# board.net
KiCad netlist of a schematic drawn in EAGLE
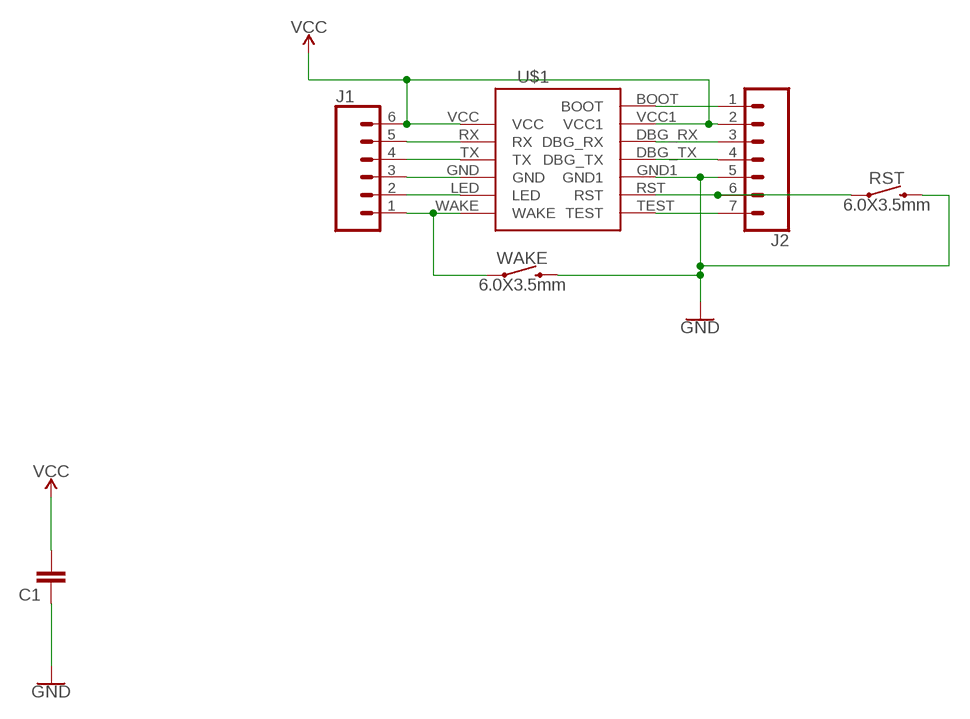
[diagram p0: schematic, sheet 1]

(export (version "E")
  (design (tool "Eeschema 10.0.6"))
  (components
    (comp (ref "C1")
      (value "C-EUC0805")
      (footprint "eagle-import:C0805")
      (libsource (lib "eagle-import") (part "C-EUC0805"))
    )
    (comp (ref "J1")
      (value "CONN_06LOCK")
      (footprint "eagle-import:1X06_LOCK")
      (libsource (lib "eagle-import") (part "CONN_06LOCK"))
    )
    (comp (ref "J2")
      (value "CONN_07LOCK")
      (footprint "eagle-import:1X07_LOCK")
      (libsource (lib "eagle-import") (part "CONN_07LOCK"))
    )
    (comp (ref "RST")
      (value "6.0X3.5mm")
      (footprint "eagle-import:TACTILE_SWITCH_SMD_6.0X3.5MM")
      (libsource (lib "eagle-import") (part "MOMENTARY-SWITCH-SPST-SMD-6.0X3.5MM"))
    )
    (comp (ref "U$1")
      (value "IM-L400")
      (footprint "eagle-import:IM-L400")
      (libsource (lib "eagle-import") (part "IM-L400"))
    )
    (comp (ref "WAKE")
      (value "6.0X3.5mm")
      (footprint "eagle-import:TACTILE_SWITCH_SMD_6.0X3.5MM")
      (libsource (lib "eagle-import") (part "MOMENTARY-SWITCH-SPST-SMD-6.0X3.5MM"))
    )
  )
  (nets
    (net (code "1") (name "GND") (class "Default")
      (node (ref "C1") (pin "1") (pinfunction "1_1") (pintype "passive"))
      (node (ref "J1") (pin "3") (pinfunction "3_3") (pintype "passive"))
      (node (ref "J2") (pin "5") (pinfunction "5_5") (pintype "passive"))
      (node (ref "RST") (pin "2") (pinfunction "2_2") (pintype "passive"))
      (node (ref "U$1") (pin "GND") (pinfunction "GND_GND") (pintype "bidirectional"))
      (node (ref "U$1") (pin "GND1") (pinfunction "GND1_GND1") (pintype "bidirectional"))
      (node (ref "WAKE") (pin "2") (pinfunction "2_2") (pintype "passive"))
    )
    (net (code "2") (name "Net-(J1-Pad1)") (class "Default")
      (node (ref "J1") (pin "1") (pinfunction "1_1") (pintype "passive"))
      (node (ref "U$1") (pin "WAKE") (pinfunction "WAKE_WAKE") (pintype "bidirectional"))
      (node (ref "WAKE") (pin "1") (pinfunction "1_1") (pintype "passive"))
    )
    (net (code "3") (name "Net-(J1-Pad2)") (class "Default")
      (node (ref "J1") (pin "2") (pinfunction "2_2") (pintype "passive"))
      (node (ref "U$1") (pin "LED") (pinfunction "LED_LED") (pintype "bidirectional"))
    )
    (net (code "4") (name "Net-(J1-Pad4)") (class "Default")
      (node (ref "J1") (pin "4") (pinfunction "4_4") (pintype "passive"))
      (node (ref "U$1") (pin "TX") (pinfunction "TX_TX") (pintype "bidirectional"))
    )
    (net (code "5") (name "Net-(J1-Pad5)") (class "Default")
      (node (ref "J1") (pin "5") (pinfunction "5_5") (pintype "passive"))
      (node (ref "U$1") (pin "RX") (pinfunction "RX_RX") (pintype "bidirectional"))
    )
    (net (code "6") (name "Net-(J2-Pad1)") (class "Default")
      (node (ref "J2") (pin "1") (pinfunction "1_1") (pintype "passive"))
      (node (ref "U$1") (pin "BOOT") (pinfunction "BOOT_BOOT") (pintype "bidirectional"))
    )
    (net (code "7") (name "Net-(J2-Pad3)") (class "Default")
      (node (ref "J2") (pin "3") (pinfunction "3_3") (pintype "passive"))
      (node (ref "U$1") (pin "DBG_RX") (pinfunction "DBG_RX_DBG_RX") (pintype "bidirectional"))
    )
    (net (code "8") (name "Net-(J2-Pad4)") (class "Default")
      (node (ref "J2") (pin "4") (pinfunction "4_4") (pintype "passive"))
      (node (ref "U$1") (pin "DBG_TX") (pinfunction "DBG_TX_DBG_TX") (pintype "bidirectional"))
    )
    (net (code "9") (name "Net-(J2-Pad6)") (class "Default")
      (node (ref "J2") (pin "6") (pinfunction "6_6") (pintype "passive"))
      (node (ref "RST") (pin "1") (pinfunction "1_1") (pintype "passive"))
      (node (ref "U$1") (pin "RST") (pinfunction "RST_RST") (pintype "bidirectional"))
    )
    (net (code "10") (name "Net-(J2-Pad7)") (class "Default")
      (node (ref "J2") (pin "7") (pinfunction "7_7") (pintype "passive"))
      (node (ref "U$1") (pin "TEST") (pinfunction "TEST_TEST") (pintype "bidirectional"))
    )
    (net (code "11") (name "VCC") (class "Default")
      (node (ref "C1") (pin "2") (pinfunction "2_2") (pintype "passive"))
      (node (ref "J1") (pin "6") (pinfunction "6_6") (pintype "passive"))
      (node (ref "J2") (pin "2") (pinfunction "2_2") (pintype "passive"))
      (node (ref "U$1") (pin "VCC") (pinfunction "VCC_VCC") (pintype "bidirectional"))
      (node (ref "U$1") (pin "VCC1") (pinfunction "VCC1_VCC1") (pintype "bidirectional"))
    )
  )
)
